# EXTERNAL_IO.net
KiCad netlist of a schematic drawn in Altium Designer
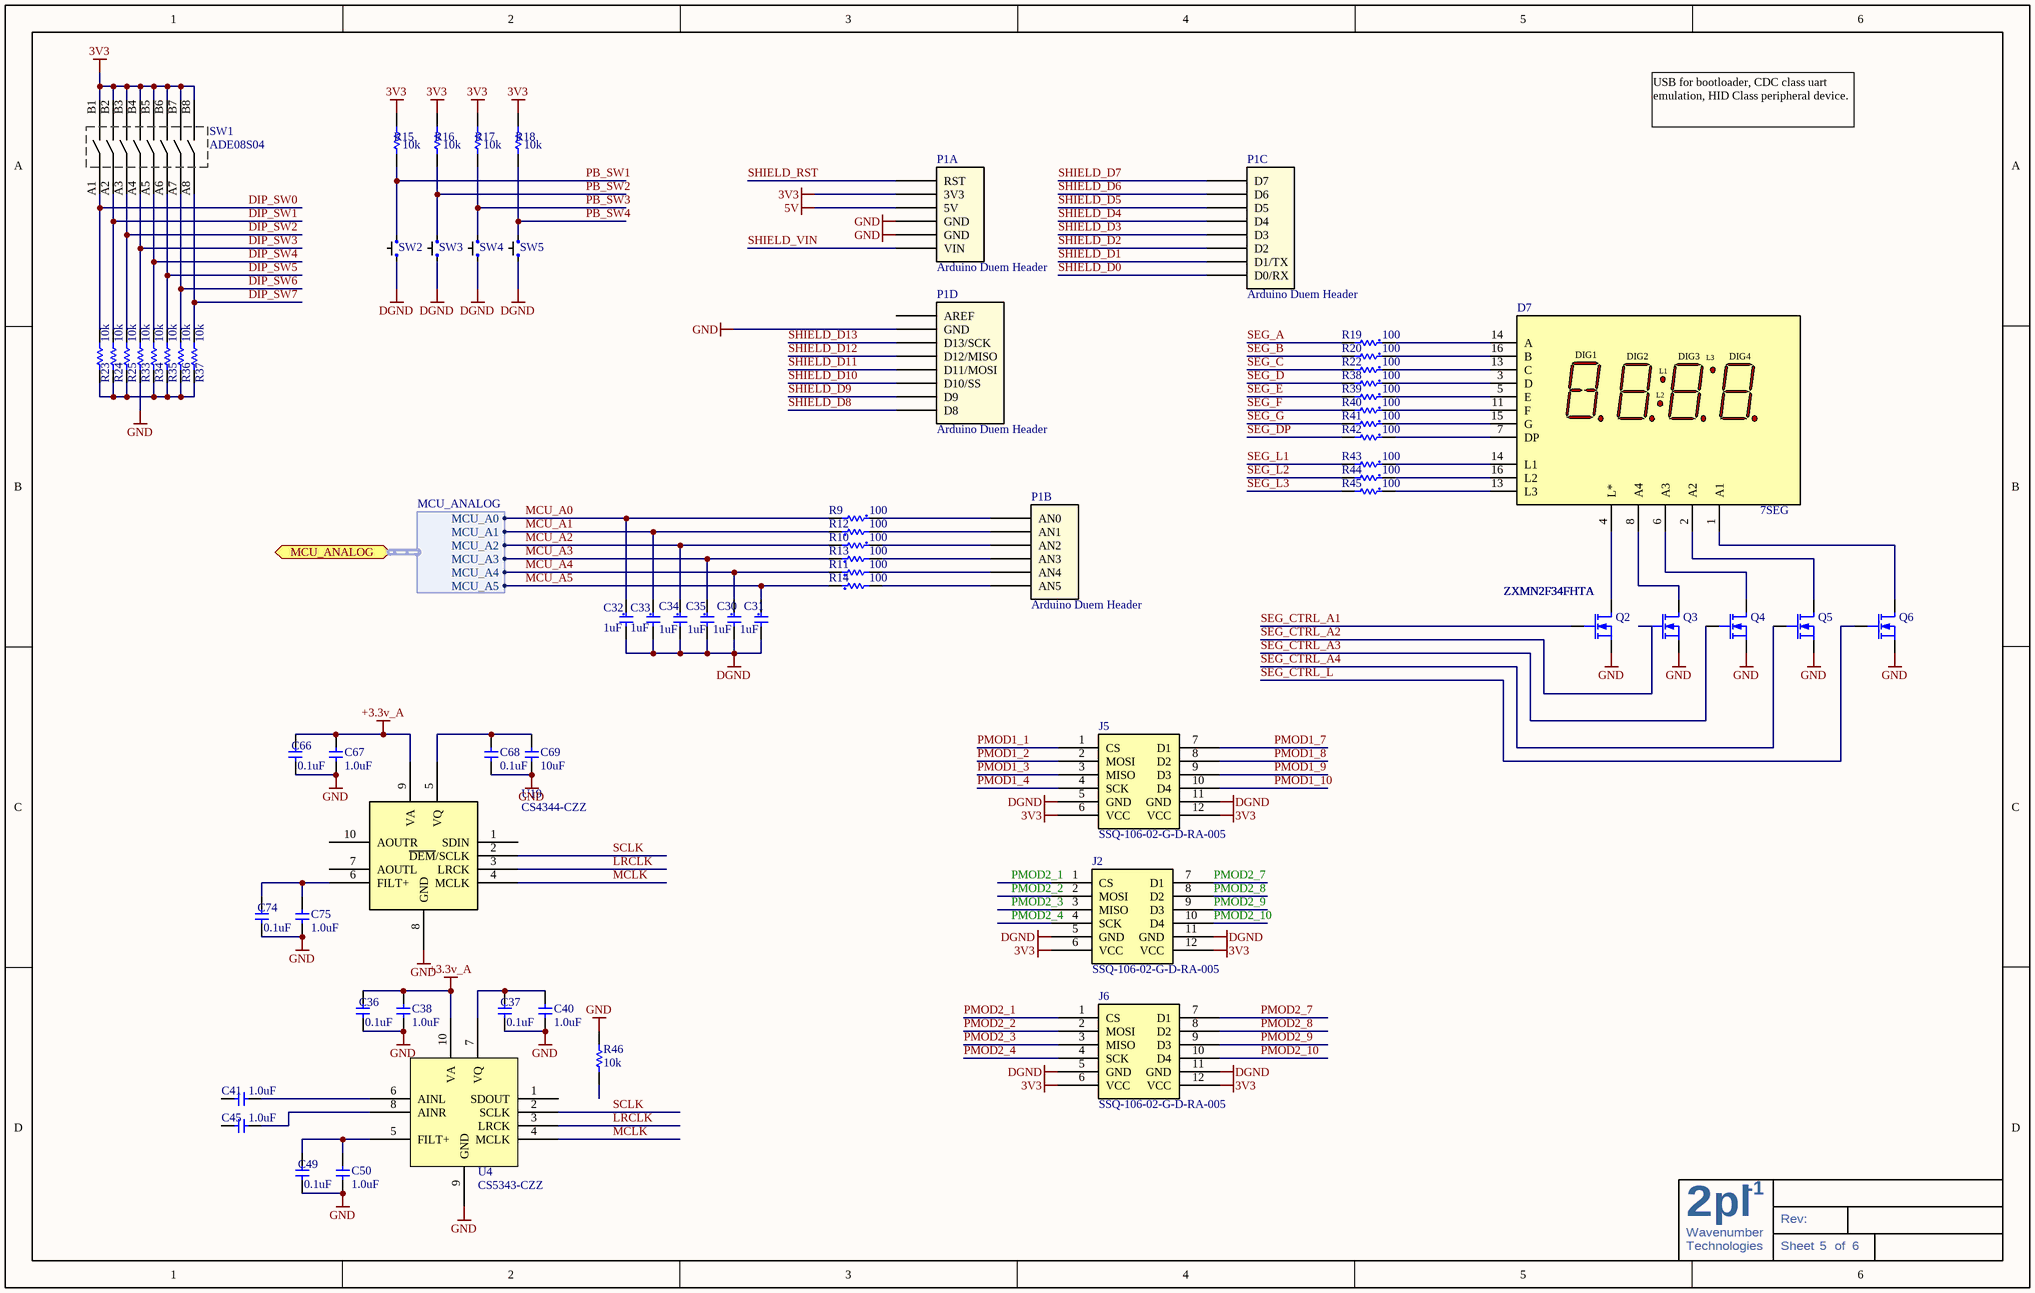
[diagram p0: EXTERNAL_IO.SchDoc]

(export (version "E")
  (design (tool "Eeschema 10.0.6"))
  (components
    (comp (ref "C30")
      (value "1uF")
      (footprint "C0603")
      (description "CAP CER .1UF 50V 10% X7R 0603")
      (fields
        (field (name "MANUFACTURER") "Murata Electronics North America")
        (field (name "MANUFACTURER PART NUMBER") "GRM188R71H104KA93D")
      )
      (libsource (lib "myGeneral") (part "Cap-Eli"))
    )
    (comp (ref "C31")
      (value "1uF")
      (footprint "C0603")
      (description "CAP CER .1UF 50V 10% X7R 0603")
      (fields
        (field (name "MANUFACTURER") "Murata Electronics North America")
        (field (name "MANUFACTURER PART NUMBER") "GRM188R71H104KA93D")
      )
      (libsource (lib "myGeneral") (part "Cap-Eli"))
    )
    (comp (ref "C32")
      (value "1uF")
      (footprint "C0603")
      (description "CAP CER .1UF 50V 10% X7R 0603")
      (fields
        (field (name "MANUFACTURER") "Murata Electronics North America")
        (field (name "MANUFACTURER PART NUMBER") "GRM188R71H104KA93D")
      )
      (libsource (lib "myGeneral") (part "Cap-Eli"))
    )
    (comp (ref "C33")
      (value "1uF")
      (footprint "C0603")
      (description "CAP CER .1UF 50V 10% X7R 0603")
      (fields
        (field (name "MANUFACTURER") "Murata Electronics North America")
        (field (name "MANUFACTURER PART NUMBER") "GRM188R71H104KA93D")
      )
      (libsource (lib "myGeneral") (part "Cap-Eli"))
    )
    (comp (ref "C34")
      (value "1uF")
      (footprint "C0603")
      (description "CAP CER .1UF 50V 10% X7R 0603")
      (fields
        (field (name "MANUFACTURER") "Murata Electronics North America")
        (field (name "MANUFACTURER PART NUMBER") "GRM188R71H104KA93D")
      )
      (libsource (lib "myGeneral") (part "Cap-Eli"))
    )
    (comp (ref "C35")
      (value "1uF")
      (footprint "C0603")
      (description "CAP CER .1UF 50V 10% X7R 0603")
      (fields
        (field (name "MANUFACTURER") "Murata Electronics North America")
        (field (name "MANUFACTURER PART NUMBER") "GRM188R71H104KA93D")
      )
      (libsource (lib "myGeneral") (part "Cap-Eli"))
    )
    (comp (ref "C36")
      (value "0.1uF")
      (footprint "C0603")
      (description "CAP CER .1UF 50V 10% X7R 0603")
      (fields
        (field (name "MANUFACTURER") "Murata Electronics North America")
        (field (name "MANUFACTURER PART NUMBER") "GRM188R71H104KA93D")
        (field (name "SOURCE") "DIGIKEY")
      )
      (libsource (lib "Playworld") (part "C"))
    )
    (comp (ref "C37")
      (value "0.1uF")
      (footprint "C0603")
      (description "CAP CER .1UF 50V 10% X7R 0603")
      (fields
        (field (name "MANUFACTURER") "Murata Electronics North America")
        (field (name "MANUFACTURER PART NUMBER") "GRM188R71H104KA93D")
        (field (name "SOURCE") "DIGIKEY")
      )
      (libsource (lib "Playworld") (part "C"))
    )
    (comp (ref "C38")
      (value "1.0uF")
      (footprint "C0805")
      (description "CAP CER 1.0UF 16V 10% X7R 0805")
      (fields
        (field (name "MANUFACTURER") "Murata Electronics North America")
        (field (name "MANUFACTURER PART NUMBER") "GRM21BR71C105KA01L")
        (field (name "SOURCE") "Digikey")
      )
      (libsource (lib "ARL_RCL") (part "GRM21BR71C105KA01L"))
    )
    (comp (ref "C40")
      (value "1.0uF")
      (footprint "C0805")
      (description "CAP CER 1.0UF 16V 10% X7R 0805")
      (fields
        (field (name "MANUFACTURER") "Murata Electronics North America")
        (field (name "MANUFACTURER PART NUMBER") "GRM21BR71C105KA01L")
        (field (name "SOURCE") "Digikey")
      )
      (libsource (lib "ARL_RCL") (part "GRM21BR71C105KA01L"))
    )
    (comp (ref "C41")
      (value "1.0uF")
      (footprint "C0805")
      (description "CAP CER 1.0UF 16V 10% X7R 0805")
      (fields
        (field (name "MANUFACTURER") "Murata Electronics North America")
        (field (name "MANUFACTURER PART NUMBER") "GRM21BR71C105KA01L")
        (field (name "SOURCE") "Digikey")
      )
      (libsource (lib "ARL_RCL") (part "GRM21BR71C105KA01L"))
    )
    (comp (ref "C45")
      (value "1.0uF")
      (footprint "C0805")
      (description "CAP CER 1.0UF 16V 10% X7R 0805")
      (fields
        (field (name "MANUFACTURER") "Murata Electronics North America")
        (field (name "MANUFACTURER PART NUMBER") "GRM21BR71C105KA01L")
        (field (name "SOURCE") "Digikey")
      )
      (libsource (lib "ARL_RCL") (part "GRM21BR71C105KA01L"))
    )
    (comp (ref "C49")
      (value "0.1uF")
      (footprint "C0603")
      (description "CAP CER .1UF 50V 10% X7R 0603")
      (fields
        (field (name "MANUFACTURER") "Murata Electronics North America")
        (field (name "MANUFACTURER PART NUMBER") "GRM188R71H104KA93D")
        (field (name "SOURCE") "DIGIKEY")
      )
      (libsource (lib "Playworld") (part "C"))
    )
    (comp (ref "C50")
      (value "1.0uF")
      (footprint "C0805")
      (description "CAP CER 1.0UF 16V 10% X7R 0805")
      (fields
        (field (name "MANUFACTURER") "Murata Electronics North America")
        (field (name "MANUFACTURER PART NUMBER") "GRM21BR71C105KA01L")
        (field (name "SOURCE") "Digikey")
      )
      (libsource (lib "ARL_RCL") (part "GRM21BR71C105KA01L"))
    )
    (comp (ref "C66")
      (value "0.1uF")
      (footprint "C0603")
      (description "CAP CER .1UF 50V 10% X7R 0603")
      (fields
        (field (name "MANUFACTURER") "Murata Electronics North America")
        (field (name "MANUFACTURER PART NUMBER") "GRM188R71H104KA93D")
        (field (name "SOURCE") "DIGIKEY")
      )
      (libsource (lib "Playworld") (part "C"))
    )
    (comp (ref "C67")
      (value "1.0uF")
      (footprint "C0805")
      (description "CAP CER 1.0UF 16V 10% X7R 0805")
      (fields
        (field (name "MANUFACTURER") "Murata Electronics North America")
        (field (name "MANUFACTURER PART NUMBER") "GRM21BR71C105KA01L")
        (field (name "SOURCE") "Digikey")
      )
      (libsource (lib "ARL_RCL") (part "GRM21BR71C105KA01L"))
    )
    (comp (ref "C68")
      (value "0.1uF")
      (footprint "C0603")
      (description "CAP CER .1UF 25V 10% X7R 0603")
      (fields
        (field (name "MANUFACTURER") "Murata Electronics North America")
        (field (name "MANUFACTURER PART NUMBER") "GRM188R71E104KA01D")
        (field (name "SOURCE") "DIGIKEY")
      )
      (libsource (lib "Playworld") (part "C"))
    )
    (comp (ref "C69")
      (value "10uF")
      (footprint "C1206")
      (description "CAP CER 10UF 10V X7R 1206")
      (fields
        (field (name "MANUFACTURER") "Murata Electronics North America")
        (field (name "MANUFACTURER PART NUMBER") "GRM31CR71A106KA01L")
        (field (name "SOURCE") "Digikey")
      )
      (libsource (lib "PlayworldRCL") (part "GRM31CR71A106KA01L"))
    )
    (comp (ref "C74")
      (value "0.1uF")
      (footprint "C0603")
      (description "CAP CER .1UF 50V 10% X7R 0603")
      (fields
        (field (name "MANUFACTURER") "Murata Electronics North America")
        (field (name "MANUFACTURER PART NUMBER") "GRM188R71H104KA93D")
        (field (name "SOURCE") "DIGIKEY")
      )
      (libsource (lib "Playworld") (part "C"))
    )
    (comp (ref "C75")
      (value "1.0uF")
      (footprint "C0805")
      (description "CAP CER 1.0UF 16V 10% X7R 0805")
      (fields
        (field (name "MANUFACTURER") "Murata Electronics North America")
        (field (name "MANUFACTURER PART NUMBER") "GRM21BR71C105KA01L")
        (field (name "SOURCE") "Digikey")
      )
      (libsource (lib "ARL_RCL") (part "GRM21BR71C105KA01L"))
    )
    (comp (ref "D7")
      (value "7SEG")
      (footprint "LED - SSEG - LTC-4727JR")
      (description "LED Displays & Accessories 4 Digit, Red Low Current")
      (fields (field (name "MANUFACTURER") "Lite-On") (field (name "MANUFACTURER PART NUMBER") "LTC-4727JR"))
      (libsource (lib "eDiode") (part "LED - SSEG - LTC-4727JR"))
    )
    (comp (ref "J2")
      (value "SSQ-106-02-G-D-RA-005")
      (footprint "PMOD Header")
      (description "SAMTEC - SSQ-106-02-G-D-RA-005 - 2MM SOCKET STRIPS")
      (fields (field (name "MANUFACTURER") "SAMTEC"))
      (libsource (lib "eConnector") (part "P-MOD"))
    )
    (comp (ref "J5")
      (value "SSQ-106-02-G-D-RA-005")
      (footprint "PMOD Header")
      (description "SAMTEC - SSQ-106-02-G-D-RA-005 - 2MM SOCKET STRIPS")
      (fields (field (name "MANUFACTURER") "SAMTEC"))
      (libsource (lib "eConnector") (part "P-MOD"))
    )
    (comp (ref "J6")
      (value "SSQ-106-02-G-D-RA-005")
      (footprint "PMOD Header")
      (description "SAMTEC - SSQ-106-02-G-D-RA-005 - 2MM SOCKET STRIPS")
      (fields (field (name "MANUFACTURER") "SAMTEC"))
      (libsource (lib "eConnector") (part "P-MOD"))
    )
    (comp (ref "P1")
      (value "Arduino Duem Header")
      (footprint "Arduino Duem Shield R1")
      (libsource (lib "eConnector") (part "Arduino Duem Header"))
    )
    (comp (ref "Q2")
      (value "ZXMN2F34FHTA")
      (footprint "SOT-23")
      (description "MOSFET N-CHAN 20V SOT23-3")
      (fields (field (name "MANUFACTURER") "Diodes/Zetex"))
      (libsource (lib "eTransistor") (part "ZXMN2F34FHTA"))
    )
    (comp (ref "Q3")
      (value "ZXMN2F34FHTA")
      (footprint "SOT-23")
      (description "MOSFET N-CHAN 20V SOT23-3")
      (fields (field (name "MANUFACTURER") "Diodes/Zetex"))
      (libsource (lib "eTransistor") (part "ZXMN2F34FHTA"))
    )
    (comp (ref "Q4")
      (value "ZXMN2F34FHTA")
      (footprint "SOT-23")
      (description "MOSFET N-CHAN 20V SOT23-3")
      (fields (field (name "MANUFACTURER") "Diodes/Zetex"))
      (libsource (lib "eTransistor") (part "ZXMN2F34FHTA"))
    )
    (comp (ref "Q5")
      (value "ZXMN2F34FHTA")
      (footprint "SOT-23")
      (description "MOSFET N-CHAN 20V SOT23-3")
      (fields (field (name "MANUFACTURER") "Diodes/Zetex"))
      (libsource (lib "eTransistor") (part "ZXMN2F34FHTA"))
    )
    (comp (ref "Q6")
      (value "ZXMN2F34FHTA")
      (footprint "SOT-23")
      (description "MOSFET N-CHAN 20V SOT23-3")
      (fields (field (name "MANUFACTURER") "Diodes/Zetex"))
      (libsource (lib "eTransistor") (part "ZXMN2F34FHTA"))
    )
    (comp (ref "R9")
      (value "100")
      (footprint "R0603")
      (description "RES 10.0K OHM 1/10W 1% 0603 SMD")
      (fields
        (field (name "MANUFACTURER") "Panasonic - ECG")
        (field (name "MANUFACTURER PART NUMBER") "ERJ-3EKF1002V")
      )
      (libsource (lib "myGeneral") (part "Res-Eli"))
    )
    (comp (ref "R10")
      (value "100")
      (footprint "R0603")
      (description "RES 10.0K OHM 1/10W 1% 0603 SMD")
      (fields
        (field (name "MANUFACTURER") "Panasonic - ECG")
        (field (name "MANUFACTURER PART NUMBER") "ERJ-3EKF1002V")
      )
      (libsource (lib "myGeneral") (part "Res-Eli"))
    )
    (comp (ref "R11")
      (value "100")
      (footprint "R0603")
      (description "RES 10.0K OHM 1/10W 1% 0603 SMD")
      (fields
        (field (name "MANUFACTURER") "Panasonic - ECG")
        (field (name "MANUFACTURER PART NUMBER") "ERJ-3EKF1002V")
      )
      (libsource (lib "myGeneral") (part "Res-Eli"))
    )
    (comp (ref "R12")
      (value "100")
      (footprint "R0603")
      (description "RES 10.0K OHM 1/10W 1% 0603 SMD")
      (fields
        (field (name "MANUFACTURER") "Panasonic - ECG")
        (field (name "MANUFACTURER PART NUMBER") "ERJ-3EKF1002V")
      )
      (libsource (lib "myGeneral") (part "Res-Eli"))
    )
    (comp (ref "R13")
      (value "100")
      (footprint "R0603")
      (description "RES 10.0K OHM 1/10W 1% 0603 SMD")
      (fields
        (field (name "MANUFACTURER") "Panasonic - ECG")
        (field (name "MANUFACTURER PART NUMBER") "ERJ-3EKF1002V")
      )
      (libsource (lib "myGeneral") (part "Res-Eli"))
    )
    (comp (ref "R14")
      (value "100")
      (footprint "R0603")
      (description "RES 10.0K OHM 1/10W 1% 0603 SMD")
      (fields
        (field (name "MANUFACTURER") "Panasonic - ECG")
        (field (name "MANUFACTURER PART NUMBER") "ERJ-3EKF1002V")
      )
      (libsource (lib "myGeneral") (part "Res-Eli"))
    )
    (comp (ref "R15")
      (value "10k")
      (footprint "R0603")
      (description "RES 10.0K OHM 1/10W 1% 0603 SMD")
      (fields
        (field (name "MANUFACTURER") "Panasonic - ECG")
        (field (name "MANUFACTURER PART NUMBER") "ERJ-3EKF1002V")
      )
      (libsource (lib "eResistors") (part "ERJ-3EKF1002V"))
    )
    (comp (ref "R16")
      (value "10k")
      (footprint "R0603")
      (description "RES 10.0K OHM 1/10W 1% 0603 SMD")
      (fields
        (field (name "MANUFACTURER") "Panasonic - ECG")
        (field (name "MANUFACTURER PART NUMBER") "ERJ-3EKF1002V")
      )
      (libsource (lib "eResistors") (part "ERJ-3EKF1002V"))
    )
    (comp (ref "R17")
      (value "10k")
      (footprint "R0603")
      (description "RES 10.0K OHM 1/10W 1% 0603 SMD")
      (fields
        (field (name "MANUFACTURER") "Panasonic - ECG")
        (field (name "MANUFACTURER PART NUMBER") "ERJ-3EKF1002V")
      )
      (libsource (lib "eResistors") (part "ERJ-3EKF1002V"))
    )
    (comp (ref "R18")
      (value "10k")
      (footprint "R0603")
      (description "RES 10.0K OHM 1/10W 1% 0603 SMD")
      (fields
        (field (name "MANUFACTURER") "Panasonic - ECG")
        (field (name "MANUFACTURER PART NUMBER") "ERJ-3EKF1002V")
      )
      (libsource (lib "eResistors") (part "ERJ-3EKF1002V"))
    )
    (comp (ref "R19")
      (value "100")
      (footprint "R0603")
      (description "RES 10.0K OHM 1/10W 1% 0603 SMD")
      (fields
        (field (name "MANUFACTURER") "Panasonic - ECG")
        (field (name "MANUFACTURER PART NUMBER") "ERJ-3EKF1002V")
      )
      (libsource (lib "myGeneral") (part "Res-Eli"))
    )
    (comp (ref "R20")
      (value "100")
      (footprint "R0603")
      (description "RES 10.0K OHM 1/10W 1% 0603 SMD")
      (fields
        (field (name "MANUFACTURER") "Panasonic - ECG")
        (field (name "MANUFACTURER PART NUMBER") "ERJ-3EKF1002V")
      )
      (libsource (lib "myGeneral") (part "Res-Eli"))
    )
    (comp (ref "R22")
      (value "100")
      (footprint "R0603")
      (description "RES 10.0K OHM 1/10W 1% 0603 SMD")
      (fields
        (field (name "MANUFACTURER") "Panasonic - ECG")
        (field (name "MANUFACTURER PART NUMBER") "ERJ-3EKF1002V")
      )
      (libsource (lib "myGeneral") (part "Res-Eli"))
    )
    (comp (ref "R23")
      (value "10k")
      (footprint "R0603")
      (description "RES 10.0K OHM 1/10W 1% 0603 SMD")
      (fields
        (field (name "MANUFACTURER") "Panasonic - ECG")
        (field (name "MANUFACTURER PART NUMBER") "ERJ-3EKF1002V")
      )
      (libsource (lib "eResistors") (part "ERJ-3EKF1002V"))
    )
    (comp (ref "R24")
      (value "10k")
      (footprint "R0603")
      (description "RES 10.0K OHM 1/10W 1% 0603 SMD")
      (fields
        (field (name "MANUFACTURER") "Panasonic - ECG")
        (field (name "MANUFACTURER PART NUMBER") "ERJ-3EKF1002V")
      )
      (libsource (lib "eResistors") (part "ERJ-3EKF1002V"))
    )
    (comp (ref "R25")
      (value "10k")
      (footprint "R0603")
      (description "RES 10.0K OHM 1/10W 1% 0603 SMD")
      (fields
        (field (name "MANUFACTURER") "Panasonic - ECG")
        (field (name "MANUFACTURER PART NUMBER") "ERJ-3EKF1002V")
      )
      (libsource (lib "eResistors") (part "ERJ-3EKF1002V"))
    )
    (comp (ref "R33")
      (value "10k")
      (footprint "R0603")
      (description "RES 10.0K OHM 1/10W 1% 0603 SMD")
      (fields
        (field (name "MANUFACTURER") "Panasonic - ECG")
        (field (name "MANUFACTURER PART NUMBER") "ERJ-3EKF1002V")
      )
      (libsource (lib "eResistors") (part "ERJ-3EKF1002V"))
    )
    (comp (ref "R34")
      (value "10k")
      (footprint "R0603")
      (description "RES 10.0K OHM 1/10W 1% 0603 SMD")
      (fields
        (field (name "MANUFACTURER") "Panasonic - ECG")
        (field (name "MANUFACTURER PART NUMBER") "ERJ-3EKF1002V")
      )
      (libsource (lib "eResistors") (part "ERJ-3EKF1002V"))
    )
    (comp (ref "R35")
      (value "10k")
      (footprint "R0603")
      (description "RES 10.0K OHM 1/10W 1% 0603 SMD")
      (fields
        (field (name "MANUFACTURER") "Panasonic - ECG")
        (field (name "MANUFACTURER PART NUMBER") "ERJ-3EKF1002V")
      )
      (libsource (lib "eResistors") (part "ERJ-3EKF1002V"))
    )
    (comp (ref "R36")
      (value "10k")
      (footprint "R0603")
      (description "RES 10.0K OHM 1/10W 1% 0603 SMD")
      (fields
        (field (name "MANUFACTURER") "Panasonic - ECG")
        (field (name "MANUFACTURER PART NUMBER") "ERJ-3EKF1002V")
      )
      (libsource (lib "eResistors") (part "ERJ-3EKF1002V"))
    )
    (comp (ref "R37")
      (value "10k")
      (footprint "R0603")
      (description "RES 10.0K OHM 1/10W 1% 0603 SMD")
      (fields
        (field (name "MANUFACTURER") "Panasonic - ECG")
        (field (name "MANUFACTURER PART NUMBER") "ERJ-3EKF1002V")
      )
      (libsource (lib "eResistors") (part "ERJ-3EKF1002V"))
    )
    (comp (ref "R38")
      (value "100")
      (footprint "R0603")
      (description "RES 10.0K OHM 1/10W 1% 0603 SMD")
      (fields
        (field (name "MANUFACTURER") "Panasonic - ECG")
        (field (name "MANUFACTURER PART NUMBER") "ERJ-3EKF1002V")
      )
      (libsource (lib "myGeneral") (part "Res-Eli"))
    )
    (comp (ref "R39")
      (value "100")
      (footprint "R0603")
      (description "RES 10.0K OHM 1/10W 1% 0603 SMD")
      (fields
        (field (name "MANUFACTURER") "Panasonic - ECG")
        (field (name "MANUFACTURER PART NUMBER") "ERJ-3EKF1002V")
      )
      (libsource (lib "myGeneral") (part "Res-Eli"))
    )
    (comp (ref "R40")
      (value "100")
      (footprint "R0603")
      (description "RES 10.0K OHM 1/10W 1% 0603 SMD")
      (fields
        (field (name "MANUFACTURER") "Panasonic - ECG")
        (field (name "MANUFACTURER PART NUMBER") "ERJ-3EKF1002V")
      )
      (libsource (lib "myGeneral") (part "Res-Eli"))
    )
    (comp (ref "R41")
      (value "100")
      (footprint "R0603")
      (description "RES 10.0K OHM 1/10W 1% 0603 SMD")
      (fields
        (field (name "MANUFACTURER") "Panasonic - ECG")
        (field (name "MANUFACTURER PART NUMBER") "ERJ-3EKF1002V")
      )
      (libsource (lib "myGeneral") (part "Res-Eli"))
    )
    (comp (ref "R42")
      (value "100")
      (footprint "R0603")
      (description "RES 10.0K OHM 1/10W 1% 0603 SMD")
      (fields
        (field (name "MANUFACTURER") "Panasonic - ECG")
        (field (name "MANUFACTURER PART NUMBER") "ERJ-3EKF1002V")
      )
      (libsource (lib "myGeneral") (part "Res-Eli"))
    )
    (comp (ref "R43")
      (value "100")
      (footprint "R0603")
      (description "RES 10.0K OHM 1/10W 1% 0603 SMD")
      (fields
        (field (name "MANUFACTURER") "Panasonic - ECG")
        (field (name "MANUFACTURER PART NUMBER") "ERJ-3EKF1002V")
      )
      (libsource (lib "myGeneral") (part "Res-Eli"))
    )
    (comp (ref "R44")
      (value "100")
      (footprint "R0603")
      (description "RES 10.0K OHM 1/10W 1% 0603 SMD")
      (fields
        (field (name "MANUFACTURER") "Panasonic - ECG")
        (field (name "MANUFACTURER PART NUMBER") "ERJ-3EKF1002V")
      )
      (libsource (lib "myGeneral") (part "Res-Eli"))
    )
    (comp (ref "R45")
      (value "100")
      (footprint "R0603")
      (description "RES 10.0K OHM 1/10W 1% 0603 SMD")
      (fields
        (field (name "MANUFACTURER") "Panasonic - ECG")
        (field (name "MANUFACTURER PART NUMBER") "ERJ-3EKF1002V")
      )
      (libsource (lib "myGeneral") (part "Res-Eli"))
    )
    (comp (ref "R46")
      (value "10k")
      (footprint "R0603")
      (description "RES 10.0K OHM 1/10W 1% 0603 SMD")
      (fields
        (field (name "MANUFACTURER") "Panasonic - ECG")
        (field (name "TOLERANCE") "±1%")
        (field (name "SOURCE") "Digikey")
      )
      (libsource (lib "eRCL") (part "ERJ-3EKF1002V"))
    )
    (comp (ref "SW1")
      (value "ADE08S04")
      (footprint "ADE08S04")
      (description "SWITCH DIP SPST EXT ACT 8POS SMD")
      (fields (field (name "MANUFACTURER") "TE Connectivity"))
      (libsource (lib "eElectroMechanical") (part "ADE08S04"))
    )
    (comp (ref "SW2")
      (value "EVQ-PAG04M")
      (footprint "EVQ-PAG04M")
      (description "6MM LIGHT TOUCH SWITCH 250GF")
      (fields (field (name "MANUFACTURER") "Panasonic - ECG") (field (name "SOURCE") "Digikey"))
      (libsource (lib "ElectroMechanical") (part "EVQ-PAG04M"))
    )
    (comp (ref "SW3")
      (value "EVQ-PAG04M")
      (footprint "EVQ-PAG04M")
      (description "6MM LIGHT TOUCH SWITCH 250GF")
      (fields (field (name "MANUFACTURER") "Panasonic - ECG") (field (name "SOURCE") "Digikey"))
      (libsource (lib "ElectroMechanical") (part "EVQ-PAG04M"))
    )
    (comp (ref "SW4")
      (value "EVQ-PAG04M")
      (footprint "EVQ-PAG04M")
      (description "6MM LIGHT TOUCH SWITCH 250GF")
      (fields (field (name "MANUFACTURER") "Panasonic - ECG") (field (name "SOURCE") "Digikey"))
      (libsource (lib "ElectroMechanical") (part "EVQ-PAG04M"))
    )
    (comp (ref "SW5")
      (value "EVQ-PAG04M")
      (footprint "EVQ-PAG04M")
      (description "6MM LIGHT TOUCH SWITCH 250GF")
      (fields (field (name "MANUFACTURER") "Panasonic - ECG") (field (name "SOURCE") "Digikey"))
      (libsource (lib "ElectroMechanical") (part "EVQ-PAG04M"))
    )
    (comp (ref "U4")
      (value "CS5343-CZZ")
      (footprint "TSSOP10")
      (description "IC ADC AUD 98DB 108KHZ 10-TSSOP")
      (fields (field (name "MANUFACTURER") "rus Logic Inc") (field (name "SOURCE") "Digikey"))
      (libsource (lib "EE417") (part "CS5343-CZZ"))
    )
    (comp (ref "U19")
      (value "CS4344-CZZ")
      (footprint "TSSOP10")
      (description "IC DAC STER 24BIT 192KHZ 10TSSOP")
      (fields (field (name "MANUFACTURER") "rus Logic Inc") (field (name "SOURCE") "Digikey"))
      (libsource (lib "eIC") (part "CS4344-CZZ"))
    )
  )
  (nets
    (net (code "2") (name "+3.3v_A") (class "Default")
      (node (ref "C36") (pin "1") (pinfunction "1_1") (pintype "passive"))
      (node (ref "C38") (pin "2") (pinfunction "2_2") (pintype "passive"))
      (node (ref "C66") (pin "1") (pinfunction "1_1") (pintype "passive"))
      (node (ref "C67") (pin "2") (pinfunction "2_2") (pintype "passive"))
      (node (ref "U19") (pin "9") (pinfunction "VA_9") (pintype "passive"))
      (node (ref "U4") (pin "10") (pinfunction "VA_10") (pintype "passive"))
    )
    (net (code "3") (name "/DIP_SW0") (class "Default")
      (node (ref "R23") (pin "2") (pinfunction "2_2") (pintype "passive"))
      (node (ref "SW1") (pin "A1") (pinfunction "A1_A1") (pintype "passive"))
    )
    (net (code "4") (name "/DIP_SW1") (class "Default")
      (node (ref "R24") (pin "2") (pinfunction "2_2") (pintype "passive"))
      (node (ref "SW1") (pin "A2") (pinfunction "A2_A2") (pintype "passive"))
    )
    (net (code "5") (name "/DIP_SW2") (class "Default")
      (node (ref "R25") (pin "2") (pinfunction "2_2") (pintype "passive"))
      (node (ref "SW1") (pin "A3") (pinfunction "A3_A3") (pintype "passive"))
    )
    (net (code "6") (name "/DIP_SW3") (class "Default")
      (node (ref "R33") (pin "2") (pinfunction "2_2") (pintype "passive"))
      (node (ref "SW1") (pin "A4") (pinfunction "A4_A4") (pintype "passive"))
    )
    (net (code "7") (name "/DIP_SW4") (class "Default")
      (node (ref "R34") (pin "2") (pinfunction "2_2") (pintype "passive"))
      (node (ref "SW1") (pin "A5") (pinfunction "A5_A5") (pintype "passive"))
    )
    (net (code "8") (name "/DIP_SW5") (class "Default")
      (node (ref "R35") (pin "2") (pinfunction "2_2") (pintype "passive"))
      (node (ref "SW1") (pin "A6") (pinfunction "A6_A6") (pintype "passive"))
    )
    (net (code "9") (name "/DIP_SW6") (class "Default")
      (node (ref "R36") (pin "2") (pinfunction "2_2") (pintype "passive"))
      (node (ref "SW1") (pin "A7") (pinfunction "A7_A7") (pintype "passive"))
    )
    (net (code "10") (name "/DIP_SW7") (class "Default")
      (node (ref "R37") (pin "2") (pinfunction "2_2") (pintype "passive"))
      (node (ref "SW1") (pin "A8") (pinfunction "A8_A8") (pintype "passive"))
    )
    (net (code "11") (name "/LRCLK") (class "Default")
      (node (ref "U19") (pin "3") (pinfunction "LRCK_3") (pintype "passive"))
      (node (ref "U4") (pin "3") (pinfunction "LRCK_3") (pintype "passive"))
    )
    (net (code "12") (name "/MCLK") (class "Default")
      (node (ref "U19") (pin "4") (pinfunction "MCLK_4") (pintype "passive"))
      (node (ref "U4") (pin "4") (pinfunction "MCLK_4") (pintype "passive"))
    )
    (net (code "13") (name "/MCU_A0") (class "Default")
      (node (ref "C32") (pin "1") (pinfunction "1_1") (pintype "passive"))
      (node (ref "R9") (pin "2") (pinfunction "2_2") (pintype "passive"))
    )
    (net (code "14") (name "/MCU_A1") (class "Default")
      (node (ref "C33") (pin "1") (pinfunction "1_1") (pintype "passive"))
      (node (ref "R12") (pin "1") (pinfunction "1_1") (pintype "passive"))
    )
    (net (code "15") (name "/MCU_A2") (class "Default")
      (node (ref "C34") (pin "1") (pinfunction "1_1") (pintype "passive"))
      (node (ref "R10") (pin "2") (pinfunction "2_2") (pintype "passive"))
    )
    (net (code "16") (name "/MCU_A3") (class "Default")
      (node (ref "C35") (pin "1") (pinfunction "1_1") (pintype "passive"))
      (node (ref "R13") (pin "1") (pinfunction "1_1") (pintype "passive"))
    )
    (net (code "17") (name "/MCU_A4") (class "Default")
      (node (ref "C30") (pin "1") (pinfunction "1_1") (pintype "passive"))
      (node (ref "R11") (pin "1") (pinfunction "1_1") (pintype "passive"))
    )
    (net (code "18") (name "/MCU_A5") (class "Default")
      (node (ref "C31") (pin "1") (pinfunction "1_1") (pintype "passive"))
      (node (ref "R14") (pin "1") (pinfunction "1_1") (pintype "passive"))
    )
    (net (code "19") (name "/PB_SW1") (class "Default")
      (node (ref "R15") (pin "1") (pinfunction "1_1") (pintype "passive"))
      (node (ref "SW2") (pin "B") (pinfunction "B_B") (pintype "passive"))
    )
    (net (code "20") (name "/PB_SW2") (class "Default")
      (node (ref "R16") (pin "1") (pinfunction "1_1") (pintype "passive"))
      (node (ref "SW3") (pin "B") (pinfunction "B_B") (pintype "passive"))
    )
    (net (code "21") (name "/PB_SW3") (class "Default")
      (node (ref "R17") (pin "1") (pinfunction "1_1") (pintype "passive"))
      (node (ref "SW4") (pin "B") (pinfunction "B_B") (pintype "passive"))
    )
    (net (code "22") (name "/PB_SW4") (class "Default")
      (node (ref "R18") (pin "1") (pinfunction "1_1") (pintype "passive"))
      (node (ref "SW5") (pin "B") (pinfunction "B_B") (pintype "passive"))
    )
    (net (code "23") (name "/PMOD1_1") (class "Default")
      (node (ref "J5") (pin "1") (pinfunction "CS_1") (pintype "power_in"))
    )
    (net (code "24") (name "/PMOD1_2") (class "Default")
      (node (ref "J5") (pin "2") (pinfunction "MOSI_2") (pintype "power_in"))
    )
    (net (code "25") (name "/PMOD1_3") (class "Default")
      (node (ref "J5") (pin "3") (pinfunction "MISO_3") (pintype "power_in"))
    )
    (net (code "26") (name "/PMOD1_4") (class "Default")
      (node (ref "J5") (pin "4") (pinfunction "SCK_4") (pintype "power_in"))
    )
    (net (code "27") (name "/PMOD1_7") (class "Default")
      (node (ref "J5") (pin "7") (pinfunction "D1_7") (pintype "power_in"))
    )
    (net (code "28") (name "/PMOD1_8") (class "Default")
      (node (ref "J5") (pin "8") (pinfunction "D2_8") (pintype "power_in"))
    )
    (net (code "29") (name "/PMOD1_9") (class "Default")
      (node (ref "J5") (pin "9") (pinfunction "D3_9") (pintype "power_in"))
    )
    (net (code "30") (name "/PMOD1_10") (class "Default")
      (node (ref "J5") (pin "10") (pinfunction "D4_10") (pintype "power_in"))
    )
    (net (code "31") (name "/PMOD2_1") (class "Default")
      (node (ref "J2") (pin "1") (pinfunction "CS_1") (pintype "power_in"))
      (node (ref "J6") (pin "1") (pinfunction "CS_1") (pintype "power_in"))
    )
    (net (code "32") (name "/PMOD2_2") (class "Default")
      (node (ref "J2") (pin "2") (pinfunction "MOSI_2") (pintype "power_in"))
      (node (ref "J6") (pin "2") (pinfunction "MOSI_2") (pintype "power_in"))
    )
    (net (code "33") (name "/PMOD2_3") (class "Default")
      (node (ref "J2") (pin "3") (pinfunction "MISO_3") (pintype "power_in"))
      (node (ref "J6") (pin "3") (pinfunction "MISO_3") (pintype "power_in"))
    )
    (net (code "34") (name "/PMOD2_4") (class "Default")
      (node (ref "J2") (pin "4") (pinfunction "SCK_4") (pintype "power_in"))
      (node (ref "J6") (pin "4") (pinfunction "SCK_4") (pintype "power_in"))
    )
    (net (code "35") (name "/PMOD2_7") (class "Default")
      (node (ref "J2") (pin "7") (pinfunction "D1_7") (pintype "power_in"))
      (node (ref "J6") (pin "7") (pinfunction "D1_7") (pintype "power_in"))
    )
    (net (code "36") (name "/PMOD2_8") (class "Default")
      (node (ref "J2") (pin "8") (pinfunction "D2_8") (pintype "power_in"))
      (node (ref "J6") (pin "8") (pinfunction "D2_8") (pintype "power_in"))
    )
    (net (code "37") (name "/PMOD2_9") (class "Default")
      (node (ref "J2") (pin "9") (pinfunction "D3_9") (pintype "power_in"))
      (node (ref "J6") (pin "9") (pinfunction "D3_9") (pintype "power_in"))
    )
    (net (code "38") (name "/PMOD2_10") (class "Default")
      (node (ref "J2") (pin "10") (pinfunction "D4_10") (pintype "power_in"))
      (node (ref "J6") (pin "10") (pinfunction "D4_10") (pintype "power_in"))
    )
    (net (code "39") (name "/SCLK") (class "Default")
      (node (ref "U19") (pin "2") (pinfunction "~{DEM}/SCLK_2") (pintype "passive"))
      (node (ref "U4") (pin "2") (pinfunction "SCLK_2") (pintype "passive"))
    )
    (net (code "40") (name "/SEG_A") (class "Default")
      (node (ref "R19") (pin "2") (pinfunction "2_2") (pintype "passive"))
    )
    (net (code "41") (name "/SEG_B") (class "Default")
      (node (ref "R20") (pin "2") (pinfunction "2_2") (pintype "passive"))
    )
    (net (code "42") (name "/SEG_C") (class "Default")
      (node (ref "R22") (pin "2") (pinfunction "2_2") (pintype "passive"))
    )
    (net (code "43") (name "/SEG_CTRL_A1") (class "Default")
      (node (ref "Q2") (pin "1") (pinfunction "G_1") (pintype "passive"))
    )
    (net (code "44") (name "/SEG_CTRL_A2") (class "Default")
      (node (ref "Q3") (pin "1") (pinfunction "G_1") (pintype "passive"))
    )
    (net (code "45") (name "/SEG_CTRL_A3") (class "Default")
      (node (ref "Q4") (pin "1") (pinfunction "G_1") (pintype "passive"))
    )
    (net (code "46") (name "/SEG_CTRL_A4") (class "Default")
      (node (ref "Q5") (pin "1") (pinfunction "G_1") (pintype "passive"))
    )
    (net (code "47") (name "/SEG_CTRL_L") (class "Default")
      (node (ref "Q6") (pin "1") (pinfunction "G_1") (pintype "passive"))
    )
    (net (code "48") (name "/SEG_D") (class "Default")
      (node (ref "R38") (pin "2") (pinfunction "2_2") (pintype "passive"))
    )
    (net (code "49") (name "/SEG_DP") (class "Default")
      (node (ref "R42") (pin "2") (pinfunction "2_2") (pintype "passive"))
    )
    (net (code "50") (name "/SEG_E") (class "Default")
      (node (ref "R39") (pin "2") (pinfunction "2_2") (pintype "passive"))
    )
    (net (code "51") (name "/SEG_F") (class "Default")
      (node (ref "R40") (pin "2") (pinfunction "2_2") (pintype "passive"))
    )
    (net (code "52") (name "/SEG_G") (class "Default")
      (node (ref "R41") (pin "2") (pinfunction "2_2") (pintype "passive"))
    )
    (net (code "53") (name "/SEG_L1") (class "Default")
      (node (ref "R43") (pin "2") (pinfunction "2_2") (pintype "passive"))
    )
    (net (code "54") (name "/SEG_L2") (class "Default")
      (node (ref "R44") (pin "2") (pinfunction "2_2") (pintype "passive"))
    )
    (net (code "55") (name "/SEG_L3") (class "Default")
      (node (ref "R45") (pin "2") (pinfunction "2_2") (pintype "passive"))
    )
    (net (code "56") (name "/SHIELD_D0") (class "Default")
      (node (ref "P1") (pin "C1") (pinfunction "D0/RX_C1") (pintype "passive"))
    )
    (net (code "57") (name "/SHIELD_D1") (class "Default")
      (node (ref "P1") (pin "C2") (pinfunction "D1/TX_C2") (pintype "passive"))
    )
    (net (code "58") (name "/SHIELD_D2") (class "Default")
      (node (ref "P1") (pin "C3") (pinfunction "D2_C3") (pintype "passive"))
    )
    (net (code "59") (name "/SHIELD_D3") (class "Default")
      (node (ref "P1") (pin "C4") (pinfunction "D3_C4") (pintype "passive"))
    )
    (net (code "60") (name "/SHIELD_D4") (class "Default")
      (node (ref "P1") (pin "C5") (pinfunction "D4_C5") (pintype "passive"))
    )
    (net (code "61") (name "/SHIELD_D5") (class "Default")
      (node (ref "P1") (pin "C6") (pinfunction "D5_C6") (pintype "passive"))
    )
    (net (code "62") (name "/SHIELD_D6") (class "Default")
      (node (ref "P1") (pin "C7") (pinfunction "D6_C7") (pintype "passive"))
    )
    (net (code "63") (name "/SHIELD_D7") (class "Default")
      (node (ref "P1") (pin "C8") (pinfunction "D7_C8") (pintype "passive"))
    )
    (net (code "64") (name "/SHIELD_D8") (class "Default")
      (node (ref "P1") (pin "D1") (pinfunction "D8_D1") (pintype "passive"))
    )
    (net (code "65") (name "/SHIELD_D9") (class "Default")
      (node (ref "P1") (pin "D2") (pinfunction "D9_D2") (pintype "passive"))
    )
    (net (code "66") (name "/SHIELD_D10") (class "Default")
      (node (ref "P1") (pin "D3") (pinfunction "D10/SS_D3") (pintype "passive"))
    )
    (net (code "67") (name "/SHIELD_D11") (class "Default")
      (node (ref "P1") (pin "D4") (pinfunction "D11/MOSI_D4") (pintype "passive"))
    )
    (net (code "68") (name "/SHIELD_D12") (class "Default")
      (node (ref "P1") (pin "D5") (pinfunction "D12/MISO_D5") (pintype "passive"))
    )
    (net (code "69") (name "/SHIELD_D13") (class "Default")
      (node (ref "P1") (pin "D6") (pinfunction "D13/SCK_D6") (pintype "passive"))
    )
    (net (code "70") (name "/SHIELD_RST") (class "Default")
      (node (ref "P1") (pin "A1") (pinfunction "RST_A1") (pintype "passive"))
    )
    (net (code "71") (name "/SHIELD_VIN") (class "Default")
      (node (ref "P1") (pin "A6") (pinfunction "VIN_A6") (pintype "passive"))
    )
    (net (code "73") (name "3V3") (class "Default")
      (node (ref "J2") (pin "12") (pinfunction "VCC_12") (pintype "power_in"))
      (node (ref "J2") (pin "6") (pinfunction "VCC_6") (pintype "power_in"))
      (node (ref "J5") (pin "12") (pinfunction "VCC_12") (pintype "power_in"))
      (node (ref "J5") (pin "6") (pinfunction "VCC_6") (pintype "power_in"))
      (node (ref "J6") (pin "12") (pinfunction "VCC_12") (pintype "power_in"))
      (node (ref "J6") (pin "6") (pinfunction "VCC_6") (pintype "power_in"))
      (node (ref "P1") (pin "A2") (pinfunction "3V3_A2") (pintype "passive"))
      (node (ref "R15") (pin "2") (pinfunction "2_2") (pintype "passive"))
      (node (ref "R16") (pin "2") (pinfunction "2_2") (pintype "passive"))
      (node (ref "R17") (pin "2") (pinfunction "2_2") (pintype "passive"))
      (node (ref "R18") (pin "2") (pinfunction "2_2") (pintype "passive"))
      (node (ref "SW1") (pin "B1") (pinfunction "B1_B1") (pintype "passive"))
      (node (ref "SW1") (pin "B2") (pinfunction "B2_B2") (pintype "passive"))
      (node (ref "SW1") (pin "B3") (pinfunction "B3_B3") (pintype "passive"))
      (node (ref "SW1") (pin "B4") (pinfunction "B4_B4") (pintype "passive"))
      (node (ref "SW1") (pin "B5") (pinfunction "B5_B5") (pintype "passive"))
      (node (ref "SW1") (pin "B6") (pinfunction "B6_B6") (pintype "passive"))
      (node (ref "SW1") (pin "B7") (pinfunction "B7_B7") (pintype "passive"))
      (node (ref "SW1") (pin "B8") (pinfunction "B8_B8") (pintype "passive"))
    )
    (net (code "74") (name "5V") (class "Default")
      (node (ref "P1") (pin "A3") (pinfunction "5V_A3") (pintype "passive"))
    )
    (net (code "75") (name "DGND") (class "Default")
      (node (ref "C30") (pin "2") (pinfunction "2_2") (pintype "passive"))
      (node (ref "C31") (pin "2") (pinfunction "2_2") (pintype "passive"))
      (node (ref "C32") (pin "2") (pinfunction "2_2") (pintype "passive"))
      (node (ref "C33") (pin "2") (pinfunction "2_2") (pintype "passive"))
      (node (ref "C34") (pin "2") (pinfunction "2_2") (pintype "passive"))
      (node (ref "C35") (pin "2") (pinfunction "2_2") (pintype "passive"))
      (node (ref "J2") (pin "11") (pinfunction "GND_11") (pintype "power_in"))
      (node (ref "J2") (pin "5") (pinfunction "GND_5") (pintype "power_in"))
      (node (ref "J5") (pin "11") (pinfunction "GND_11") (pintype "power_in"))
      (node (ref "J5") (pin "5") (pinfunction "GND_5") (pintype "power_in"))
      (node (ref "J6") (pin "11") (pinfunction "GND_11") (pintype "power_in"))
      (node (ref "J6") (pin "5") (pinfunction "GND_5") (pintype "power_in"))
      (node (ref "SW2") (pin "A") (pinfunction "A_A") (pintype "passive"))
      (node (ref "SW3") (pin "A") (pinfunction "A_A") (pintype "passive"))
      (node (ref "SW4") (pin "A") (pinfunction "A_A") (pintype "passive"))
      (node (ref "SW5") (pin "A") (pinfunction "A_A") (pintype "passive"))
    )
    (net (code "76") (name "GND") (class "Default")
      (node (ref "C36") (pin "2") (pinfunction "2_2") (pintype "passive"))
      (node (ref "C37") (pin "2") (pinfunction "2_2") (pintype "passive"))
      (node (ref "C38") (pin "1") (pinfunction "1_1") (pintype "passive"))
      (node (ref "C40") (pin "1") (pinfunction "1_1") (pintype "passive"))
      (node (ref "C49") (pin "2") (pinfunction "2_2") (pintype "passive"))
      (node (ref "C50") (pin "1") (pinfunction "1_1") (pintype "passive"))
      (node (ref "C66") (pin "2") (pinfunction "2_2") (pintype "passive"))
      (node (ref "C67") (pin "1") (pinfunction "1_1") (pintype "passive"))
      (node (ref "C68") (pin "2") (pinfunction "2_2") (pintype "passive"))
      (node (ref "C69") (pin "1") (pinfunction "1_1") (pintype "passive"))
      (node (ref "C74") (pin "2") (pinfunction "2_2") (pintype "passive"))
      (node (ref "C75") (pin "1") (pinfunction "1_1") (pintype "passive"))
      (node (ref "P1") (pin "A4") (pinfunction "GND_A4") (pintype "passive"))
      (node (ref "P1") (pin "A5") (pinfunction "GND_A5") (pintype "passive"))
      (node (ref "P1") (pin "D7") (pinfunction "GND_D7") (pintype "passive"))
      (node (ref "Q2") (pin "2") (pinfunction "2_2") (pintype "passive"))
      (node (ref "Q3") (pin "2") (pinfunction "2_2") (pintype "passive"))
      (node (ref "Q4") (pin "2") (pinfunction "2_2") (pintype "passive"))
      (node (ref "Q5") (pin "2") (pinfunction "2_2") (pintype "passive"))
      (node (ref "Q6") (pin "2") (pinfunction "2_2") (pintype "passive"))
      (node (ref "R33") (pin "1") (pinfunction "1_1") (pintype "passive"))
      (node (ref "R46") (pin "2") (pinfunction "2_2") (pintype "passive"))
      (node (ref "U19") (pin "8") (pinfunction "GND_8") (pintype "passive"))
      (node (ref "U4") (pin "9") (pinfunction "GND_9") (pintype "passive"))
    )
    (net (code "77") (name "Net-(D7-A)") (class "Default")
      (node (ref "D7") (pin "14") (pinfunction "A_14") (pintype "passive"))
      (node (ref "R19") (pin "1") (pinfunction "1_1") (pintype "passive"))
    )
    (net (code "78") (name "Net-(D7-A1)") (class "Default")
      (node (ref "D7") (pin "1") (pinfunction "A1_1") (pintype "passive"))
      (node (ref "Q6") (pin "3") (pinfunction "D_3") (pintype "passive"))
    )
    (net (code "79") (name "Net-(D7-A2)") (class "Default")
      (node (ref "D7") (pin "2") (pinfunction "A2_2") (pintype "passive"))
      (node (ref "Q5") (pin "3") (pinfunction "D_3") (pintype "passive"))
    )
    (net (code "80") (name "Net-(D7-A3)") (class "Default")
      (node (ref "D7") (pin "6") (pinfunction "A3_6") (pintype "passive"))
      (node (ref "Q4") (pin "3") (pinfunction "D_3") (pintype "passive"))
    )
    (net (code "81") (name "Net-(D7-A4)") (class "Default")
      (node (ref "D7") (pin "8") (pinfunction "A4_8") (pintype "passive"))
      (node (ref "Q3") (pin "3") (pinfunction "D_3") (pintype "passive"))
    )
    (net (code "82") (name "Net-(D7-B)") (class "Default")
      (node (ref "D7") (pin "16") (pinfunction "B_16") (pintype "passive"))
      (node (ref "R20") (pin "1") (pinfunction "1_1") (pintype "passive"))
    )
    (net (code "83") (name "Net-(D7-C)") (class "Default")
      (node (ref "D7") (pin "13") (pinfunction "C_13") (pintype "passive"))
      (node (ref "R22") (pin "1") (pinfunction "1_1") (pintype "passive"))
    )
    (net (code "84") (name "Net-(D7-D)") (class "Default")
      (node (ref "D7") (pin "3") (pinfunction "D_3") (pintype "passive"))
      (node (ref "R38") (pin "1") (pinfunction "1_1") (pintype "passive"))
    )
    (net (code "85") (name "Net-(D7-DP)") (class "Default")
      (node (ref "D7") (pin "7") (pinfunction "DP_7") (pintype "passive"))
      (node (ref "R42") (pin "1") (pinfunction "1_1") (pintype "passive"))
    )
    (net (code "86") (name "Net-(D7-E)") (class "Default")
      (node (ref "D7") (pin "5") (pinfunction "E_5") (pintype "passive"))
      (node (ref "R39") (pin "1") (pinfunction "1_1") (pintype "passive"))
    )
    (net (code "87") (name "Net-(D7-F)") (class "Default")
      (node (ref "D7") (pin "11") (pinfunction "F_11") (pintype "passive"))
      (node (ref "R40") (pin "1") (pinfunction "1_1") (pintype "passive"))
    )
    (net (code "88") (name "Net-(D7-G)") (class "Default")
      (node (ref "D7") (pin "15") (pinfunction "G_15") (pintype "passive"))
      (node (ref "R41") (pin "1") (pinfunction "1_1") (pintype "passive"))
    )
    (net (code "89") (name "Net-(D7-L*)") (class "Default")
      (node (ref "D7") (pin "4") (pinfunction "L*_4") (pintype "passive"))
      (node (ref "Q2") (pin "3") (pinfunction "D_3") (pintype "passive"))
    )
    (net (code "90") (name "Net-(D7-L1)") (class "Default")
      (node (ref "D7") (pin "14") (pinfunction "L1_14") (pintype "passive"))
      (node (ref "R43") (pin "1") (pinfunction "1_1") (pintype "passive"))
    )
    (net (code "91") (name "Net-(D7-L2)") (class "Default")
      (node (ref "D7") (pin "16") (pinfunction "L2_16") (pintype "passive"))
      (node (ref "R44") (pin "1") (pinfunction "1_1") (pintype "passive"))
    )
    (net (code "92") (name "Net-(D7-L3)") (class "Default")
      (node (ref "D7") (pin "13") (pinfunction "L3_13") (pintype "passive"))
      (node (ref "R45") (pin "1") (pinfunction "1_1") (pintype "passive"))
    )
    (net (code "93") (name "Net-(P1B-AN0)") (class "Default")
      (node (ref "P1") (pin "B1") (pinfunction "AN0_B1") (pintype "passive"))
      (node (ref "R9") (pin "1") (pinfunction "1_1") (pintype "passive"))
    )
    (net (code "94") (name "Net-(P1B-AN1)") (class "Default")
      (node (ref "P1") (pin "B2") (pinfunction "AN1_B2") (pintype "passive"))
      (node (ref "R12") (pin "2") (pinfunction "2_2") (pintype "passive"))
    )
    (net (code "95") (name "Net-(P1B-AN2)") (class "Default")
      (node (ref "P1") (pin "B3") (pinfunction "AN2_B3") (pintype "passive"))
      (node (ref "R10") (pin "1") (pinfunction "1_1") (pintype "passive"))
    )
    (net (code "96") (name "Net-(P1B-AN3)") (class "Default")
      (node (ref "P1") (pin "B4") (pinfunction "AN3_B4") (pintype "passive"))
      (node (ref "R13") (pin "2") (pinfunction "2_2") (pintype "passive"))
    )
    (net (code "97") (name "Net-(P1B-AN4)") (class "Default")
      (node (ref "P1") (pin "B5") (pinfunction "AN4_B5") (pintype "passive"))
      (node (ref "R11") (pin "2") (pinfunction "2_2") (pintype "passive"))
    )
    (net (code "98") (name "Net-(P1B-AN5)") (class "Default")
      (node (ref "P1") (pin "B6") (pinfunction "AN5_B6") (pintype "passive"))
      (node (ref "R14") (pin "2") (pinfunction "2_2") (pintype "passive"))
    )
    (net (code "99") (name "Net-(R23-Pad1)") (class "Default")
      (node (ref "R23") (pin "1") (pinfunction "1_1") (pintype "passive"))
      (node (ref "R24") (pin "1") (pinfunction "1_1") (pintype "passive"))
      (node (ref "R25") (pin "1") (pinfunction "1_1") (pintype "passive"))
      (node (ref "R34") (pin "1") (pinfunction "1_1") (pintype "passive"))
      (node (ref "R35") (pin "1") (pinfunction "1_1") (pintype "passive"))
      (node (ref "R36") (pin "1") (pinfunction "1_1") (pintype "passive"))
      (node (ref "R37") (pin "1") (pinfunction "1_1") (pintype "passive"))
    )
    (net (code "100") (name "Net-(U4-AINL)") (class "Default")
      (node (ref "C41") (pin "1") (pinfunction "1_1") (pintype "passive"))
      (node (ref "U4") (pin "6") (pinfunction "AINL_6") (pintype "passive"))
    )
    (net (code "101") (name "Net-(U4-AINR)") (class "Default")
      (node (ref "C45") (pin "1") (pinfunction "1_1") (pintype "passive"))
      (node (ref "U4") (pin "8") (pinfunction "AINR_8") (pintype "passive"))
    )
    (net (code "102") (name "Net-(U4-FILT+)") (class "Default")
      (node (ref "C49") (pin "1") (pinfunction "1_1") (pintype "passive"))
      (node (ref "C50") (pin "2") (pinfunction "2_2") (pintype "passive"))
      (node (ref "U4") (pin "5") (pinfunction "FILT+_5") (pintype "passive"))
    )
    (net (code "103") (name "Net-(U4-VQ)") (class "Default")
      (node (ref "C37") (pin "1") (pinfunction "1_1") (pintype "passive"))
      (node (ref "C40") (pin "2") (pinfunction "2_2") (pintype "passive"))
      (node (ref "U4") (pin "7") (pinfunction "VQ_7") (pintype "passive"))
    )
    (net (code "104") (name "Net-(U19-FILT+)") (class "Default")
      (node (ref "C74") (pin "1") (pinfunction "1_1") (pintype "passive"))
      (node (ref "C75") (pin "2") (pinfunction "2_2") (pintype "passive"))
      (node (ref "U19") (pin "6") (pinfunction "FILT+_6") (pintype "passive"))
    )
    (net (code "105") (name "Net-(U19-VQ)") (class "Default")
      (node (ref "C68") (pin "1") (pinfunction "1_1") (pintype "passive"))
      (node (ref "C69") (pin "2") (pinfunction "2_2") (pintype "passive"))
      (node (ref "U19") (pin "5") (pinfunction "VQ_5") (pintype "passive"))
    )
    (net (code "106") (name "unconnected-(C41-Pad2)") (class "Default")
      (node (ref "C41") (pin "2") (pinfunction "2_2") (pintype "passive"))
    )
    (net (code "107") (name "unconnected-(C45-Pad2)") (class "Default")
      (node (ref "C45") (pin "2") (pinfunction "2_2") (pintype "passive"))
    )
    (net (code "108") (name "unconnected-(P1D-AREF-PadD8)") (class "Default")
      (node (ref "P1") (pin "D8") (pinfunction "AREF_D8") (pintype "passive"))
    )
    (net (code "109") (name "unconnected-(R46-Pad1)") (class "Default")
      (node (ref "R46") (pin "1") (pinfunction "1_1") (pintype "passive"))
    )
    (net (code "110") (name "unconnected-(U4-SDOUT-Pad1)") (class "Default")
      (node (ref "U4") (pin "1") (pinfunction "SDOUT_1") (pintype "passive"))
    )
    (net (code "111") (name "unconnected-(U19-AOUTL-Pad7)") (class "Default")
      (node (ref "U19") (pin "7") (pinfunction "AOUTL_7") (pintype "passive"))
    )
    (net (code "112") (name "unconnected-(U19-AOUTR-Pad10)") (class "Default")
      (node (ref "U19") (pin "10") (pinfunction "AOUTR_10") (pintype "passive"))
    )
    (net (code "113") (name "unconnected-(U19-SDIN-Pad1)") (class "Default")
      (node (ref "U19") (pin "1") (pinfunction "SDIN_1") (pintype "passive"))
    )
  )
)
